# R122X.net
KiCad netlist of a schematic drawn in EAGLE
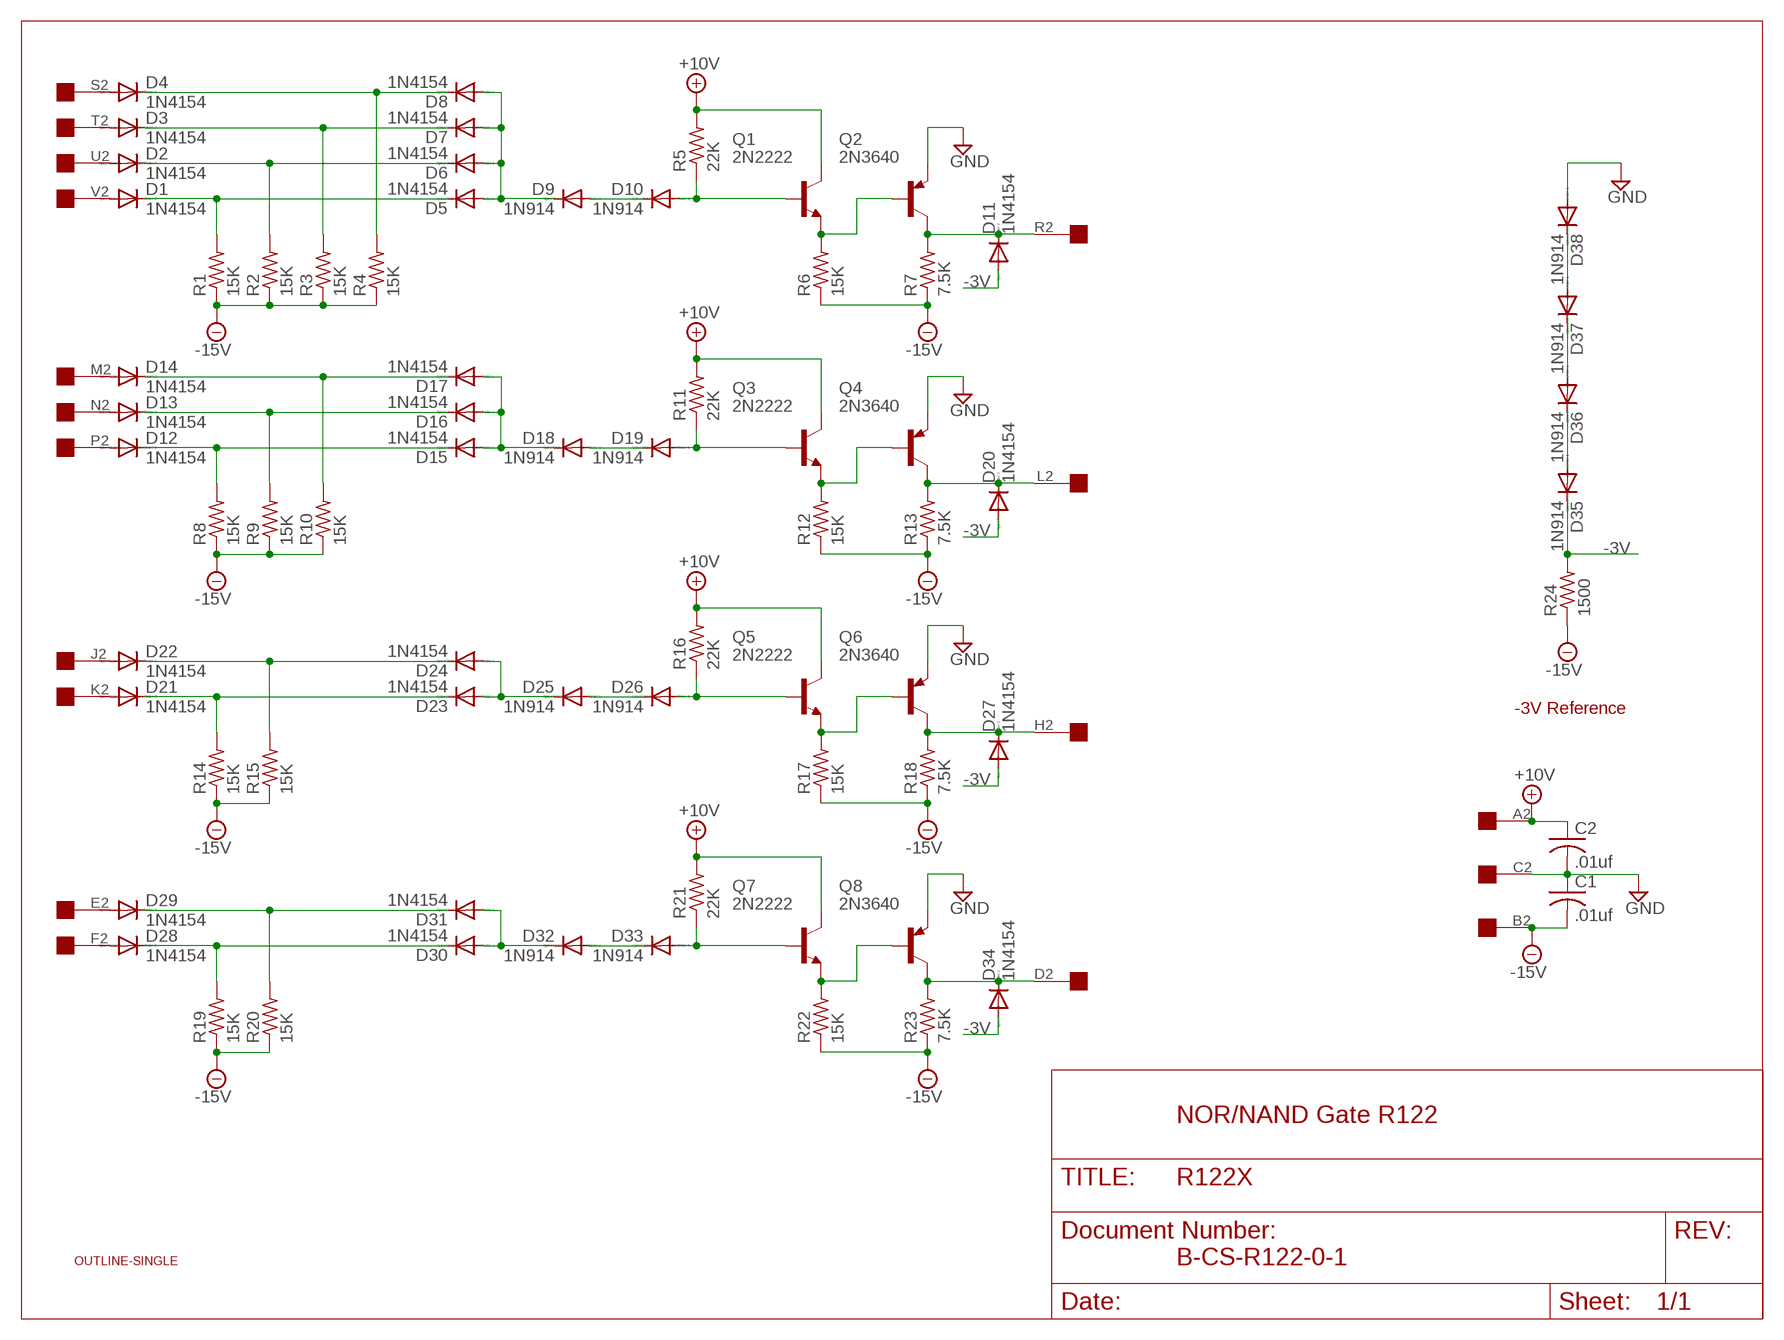
[diagram p0: schematic, sheet 1]

(export (version "E")
  (design (tool "Eeschema 10.0.6"))
  (components
    (comp (ref "C1")
      (value ".01uf")
      (footprint "eagle-import:C050-025X075")
      (libsource (lib "eagle-import") (part "C-US050-025X075"))
    )
    (comp (ref "C2")
      (value ".01uf")
      (footprint "eagle-import:C050-025X075")
      (libsource (lib "eagle-import") (part "C-US050-025X075"))
    )
    (comp (ref "D1")
      (value "1N4154")
      (footprint "eagle-import:DO35-10")
      (libsource (lib "eagle-import") (part "1N4148DO35-10"))
    )
    (comp (ref "D2")
      (value "1N4154")
      (footprint "eagle-import:DO35-10")
      (libsource (lib "eagle-import") (part "1N4148DO35-10"))
    )
    (comp (ref "D3")
      (value "1N4154")
      (footprint "eagle-import:DO35-10")
      (libsource (lib "eagle-import") (part "1N4148DO35-10"))
    )
    (comp (ref "D4")
      (value "1N4154")
      (footprint "eagle-import:DO35-10")
      (libsource (lib "eagle-import") (part "1N4148DO35-10"))
    )
    (comp (ref "D5")
      (value "1N4154")
      (footprint "eagle-import:DO35-10")
      (libsource (lib "eagle-import") (part "1N4148DO35-10"))
    )
    (comp (ref "D6")
      (value "1N4154")
      (footprint "eagle-import:DO35-10")
      (libsource (lib "eagle-import") (part "1N4148DO35-10"))
    )
    (comp (ref "D7")
      (value "1N4154")
      (footprint "eagle-import:DO35-10")
      (libsource (lib "eagle-import") (part "1N4148DO35-10"))
    )
    (comp (ref "D8")
      (value "1N4154")
      (footprint "eagle-import:DO35-10")
      (libsource (lib "eagle-import") (part "1N4148DO35-10"))
    )
    (comp (ref "D9")
      (value "1N914")
      (footprint "eagle-import:DO35-10")
      (libsource (lib "eagle-import") (part "1N4148DO35-10"))
    )
    (comp (ref "D10")
      (value "1N914")
      (footprint "eagle-import:DO35-10")
      (libsource (lib "eagle-import") (part "1N4148DO35-10"))
    )
    (comp (ref "D11")
      (value "1N4154")
      (footprint "eagle-import:DO35-10")
      (libsource (lib "eagle-import") (part "1N4148DO35-10"))
    )
    (comp (ref "D12")
      (value "1N4154")
      (footprint "eagle-import:DO35-10")
      (libsource (lib "eagle-import") (part "1N4148DO35-10"))
    )
    (comp (ref "D13")
      (value "1N4154")
      (footprint "eagle-import:DO35-10")
      (libsource (lib "eagle-import") (part "1N4148DO35-10"))
    )
    (comp (ref "D14")
      (value "1N4154")
      (footprint "eagle-import:DO35-10")
      (libsource (lib "eagle-import") (part "1N4148DO35-10"))
    )
    (comp (ref "D15")
      (value "1N4154")
      (footprint "eagle-import:DO35-10")
      (libsource (lib "eagle-import") (part "1N4148DO35-10"))
    )
    (comp (ref "D16")
      (value "1N4154")
      (footprint "eagle-import:DO35-10")
      (libsource (lib "eagle-import") (part "1N4148DO35-10"))
    )
    (comp (ref "D17")
      (value "1N4154")
      (footprint "eagle-import:DO35-10")
      (libsource (lib "eagle-import") (part "1N4148DO35-10"))
    )
    (comp (ref "D18")
      (value "1N914")
      (footprint "eagle-import:DO35-10")
      (libsource (lib "eagle-import") (part "1N4148DO35-10"))
    )
    (comp (ref "D19")
      (value "1N914")
      (footprint "eagle-import:DO35-10")
      (libsource (lib "eagle-import") (part "1N4148DO35-10"))
    )
    (comp (ref "D20")
      (value "1N4154")
      (footprint "eagle-import:DO35-10")
      (libsource (lib "eagle-import") (part "1N4148DO35-10"))
    )
    (comp (ref "D21")
      (value "1N4154")
      (footprint "eagle-import:DO35-10")
      (libsource (lib "eagle-import") (part "1N4148DO35-10"))
    )
    (comp (ref "D22")
      (value "1N4154")
      (footprint "eagle-import:DO35-10")
      (libsource (lib "eagle-import") (part "1N4148DO35-10"))
    )
    (comp (ref "D23")
      (value "1N4154")
      (footprint "eagle-import:DO35-10")
      (libsource (lib "eagle-import") (part "1N4148DO35-10"))
    )
    (comp (ref "D24")
      (value "1N4154")
      (footprint "eagle-import:DO35-10")
      (libsource (lib "eagle-import") (part "1N4148DO35-10"))
    )
    (comp (ref "D25")
      (value "1N914")
      (footprint "eagle-import:DO35-10")
      (libsource (lib "eagle-import") (part "1N4148DO35-10"))
    )
    (comp (ref "D26")
      (value "1N914")
      (footprint "eagle-import:DO35-10")
      (libsource (lib "eagle-import") (part "1N4148DO35-10"))
    )
    (comp (ref "D27")
      (value "1N4154")
      (footprint "eagle-import:DO35-10")
      (libsource (lib "eagle-import") (part "1N4148DO35-10"))
    )
    (comp (ref "D28")
      (value "1N4154")
      (footprint "eagle-import:DO35-10")
      (libsource (lib "eagle-import") (part "1N4148DO35-10"))
    )
    (comp (ref "D29")
      (value "1N4154")
      (footprint "eagle-import:DO35-10")
      (libsource (lib "eagle-import") (part "1N4148DO35-10"))
    )
    (comp (ref "D30")
      (value "1N4154")
      (footprint "eagle-import:DO35-10")
      (libsource (lib "eagle-import") (part "1N4148DO35-10"))
    )
    (comp (ref "D31")
      (value "1N4154")
      (footprint "eagle-import:DO35-10")
      (libsource (lib "eagle-import") (part "1N4148DO35-10"))
    )
    (comp (ref "D32")
      (value "1N914")
      (footprint "eagle-import:DO35-10")
      (libsource (lib "eagle-import") (part "1N4148DO35-10"))
    )
    (comp (ref "D33")
      (value "1N914")
      (footprint "eagle-import:DO35-10")
      (libsource (lib "eagle-import") (part "1N4148DO35-10"))
    )
    (comp (ref "D34")
      (value "1N4154")
      (footprint "eagle-import:DO35-10")
      (libsource (lib "eagle-import") (part "1N4148DO35-10"))
    )
    (comp (ref "D35")
      (value "1N914")
      (footprint "eagle-import:DO35-10")
      (libsource (lib "eagle-import") (part "1N4148DO35-10"))
    )
    (comp (ref "D36")
      (value "1N914")
      (footprint "eagle-import:DO35-10")
      (libsource (lib "eagle-import") (part "1N4148DO35-10"))
    )
    (comp (ref "D37")
      (value "1N914")
      (footprint "eagle-import:DO35-10")
      (libsource (lib "eagle-import") (part "1N4148DO35-10"))
    )
    (comp (ref "D38")
      (value "1N914")
      (footprint "eagle-import:DO35-10")
      (libsource (lib "eagle-import") (part "1N4148DO35-10"))
    )
    (comp (ref "Q1")
      (value "2N2222")
      (footprint "eagle-import:TO39")
      (libsource (lib "eagle-import") (part "-NPN-TO39-EBC2N1711"))
    )
    (comp (ref "Q2")
      (value "2N3640")
      (footprint "eagle-import:TO39")
      (libsource (lib "eagle-import") (part "2N3637"))
    )
    (comp (ref "Q3")
      (value "2N2222")
      (footprint "eagle-import:TO39")
      (libsource (lib "eagle-import") (part "-NPN-TO39-EBC2N1711"))
    )
    (comp (ref "Q4")
      (value "2N3640")
      (footprint "eagle-import:TO39")
      (libsource (lib "eagle-import") (part "2N3637"))
    )
    (comp (ref "Q5")
      (value "2N2222")
      (footprint "eagle-import:TO39")
      (libsource (lib "eagle-import") (part "-NPN-TO39-EBC2N1711"))
    )
    (comp (ref "Q6")
      (value "2N3640")
      (footprint "eagle-import:TO39")
      (libsource (lib "eagle-import") (part "2N3637"))
    )
    (comp (ref "Q7")
      (value "2N2222")
      (footprint "eagle-import:TO39")
      (libsource (lib "eagle-import") (part "-NPN-TO39-EBC2N1711"))
    )
    (comp (ref "Q8")
      (value "2N3640")
      (footprint "eagle-import:TO39")
      (libsource (lib "eagle-import") (part "2N3637"))
    )
    (comp (ref "R1")
      (value "15K")
      (footprint "eagle-import:0207_10")
      (libsource (lib "eagle-import") (part "R-US_0207/10"))
    )
    (comp (ref "R2")
      (value "15K")
      (footprint "eagle-import:0207_10")
      (libsource (lib "eagle-import") (part "R-US_0207/10"))
    )
    (comp (ref "R3")
      (value "15K")
      (footprint "eagle-import:0207_10")
      (libsource (lib "eagle-import") (part "R-US_0207/10"))
    )
    (comp (ref "R4")
      (value "15K")
      (footprint "eagle-import:0207_10")
      (libsource (lib "eagle-import") (part "R-US_0207/10"))
    )
    (comp (ref "R5")
      (value "22K")
      (footprint "eagle-import:0207_10")
      (libsource (lib "eagle-import") (part "R-US_0207/10"))
    )
    (comp (ref "R6")
      (value "15K")
      (footprint "eagle-import:0207_10")
      (libsource (lib "eagle-import") (part "R-US_0207/10"))
    )
    (comp (ref "R7")
      (value "7.5K")
      (footprint "eagle-import:0207_10")
      (libsource (lib "eagle-import") (part "R-US_0207/10"))
    )
    (comp (ref "R8")
      (value "15K")
      (footprint "eagle-import:0207_10")
      (libsource (lib "eagle-import") (part "R-US_0207/10"))
    )
    (comp (ref "R9")
      (value "15K")
      (footprint "eagle-import:0207_10")
      (libsource (lib "eagle-import") (part "R-US_0207/10"))
    )
    (comp (ref "R10")
      (value "15K")
      (footprint "eagle-import:0207_10")
      (libsource (lib "eagle-import") (part "R-US_0207/10"))
    )
    (comp (ref "R11")
      (value "22K")
      (footprint "eagle-import:0207_10")
      (libsource (lib "eagle-import") (part "R-US_0207/10"))
    )
    (comp (ref "R12")
      (value "15K")
      (footprint "eagle-import:0207_10")
      (libsource (lib "eagle-import") (part "R-US_0207/10"))
    )
    (comp (ref "R13")
      (value "7.5K")
      (footprint "eagle-import:0207_10")
      (libsource (lib "eagle-import") (part "R-US_0207/10"))
    )
    (comp (ref "R14")
      (value "15K")
      (footprint "eagle-import:0207_10")
      (libsource (lib "eagle-import") (part "R-US_0207/10"))
    )
    (comp (ref "R15")
      (value "15K")
      (footprint "eagle-import:0207_10")
      (libsource (lib "eagle-import") (part "R-US_0207/10"))
    )
    (comp (ref "R16")
      (value "22K")
      (footprint "eagle-import:0207_10")
      (libsource (lib "eagle-import") (part "R-US_0207/10"))
    )
    (comp (ref "R17")
      (value "15K")
      (footprint "eagle-import:0207_10")
      (libsource (lib "eagle-import") (part "R-US_0207/10"))
    )
    (comp (ref "R18")
      (value "7.5K")
      (footprint "eagle-import:0207_10")
      (libsource (lib "eagle-import") (part "R-US_0207/10"))
    )
    (comp (ref "R19")
      (value "15K")
      (footprint "eagle-import:0207_10")
      (libsource (lib "eagle-import") (part "R-US_0207/10"))
    )
    (comp (ref "R20")
      (value "15K")
      (footprint "eagle-import:0207_10")
      (libsource (lib "eagle-import") (part "R-US_0207/10"))
    )
    (comp (ref "R21")
      (value "22K")
      (footprint "eagle-import:0207_10")
      (libsource (lib "eagle-import") (part "R-US_0207/10"))
    )
    (comp (ref "R22")
      (value "15K")
      (footprint "eagle-import:0207_10")
      (libsource (lib "eagle-import") (part "R-US_0207/10"))
    )
    (comp (ref "R23")
      (value "7.5K")
      (footprint "eagle-import:0207_10")
      (libsource (lib "eagle-import") (part "R-US_0207/10"))
    )
    (comp (ref "R24")
      (value "1500")
      (footprint "eagle-import:0207_10")
      (libsource (lib "eagle-import") (part "R-US_0207/10"))
    )
    (comp (ref "U$1")
      (value "OUTLINE-SINGLE")
      (footprint "eagle-import:SINGLE")
      (libsource (lib "eagle-import") (part "OUTLINE-SINGLE"))
    )
    (comp (ref "U$2")
      (value "EDGE-1")
      (footprint "eagle-import:EDGE-CON1")
      (libsource (lib "eagle-import") (part "EDGE-1"))
    )
  )
  (nets
    (net (code "1") (name "+10V") (class "Default")
      (node (ref "C2") (pin "1") (pinfunction "1_1") (pintype "passive"))
      (node (ref "Q1") (pin "3") (pinfunction "C_3") (pintype "passive"))
      (node (ref "Q3") (pin "3") (pinfunction "C_3") (pintype "passive"))
      (node (ref "Q5") (pin "3") (pinfunction "C_3") (pintype "passive"))
      (node (ref "Q7") (pin "3") (pinfunction "C_3") (pintype "passive"))
      (node (ref "R11") (pin "2") (pinfunction "2_2") (pintype "passive"))
      (node (ref "R16") (pin "2") (pinfunction "2_2") (pintype "passive"))
      (node (ref "R21") (pin "2") (pinfunction "2_2") (pintype "passive"))
      (node (ref "R5") (pin "2") (pinfunction "2_2") (pintype "passive"))
      (node (ref "U$2") (pin "A2") (pinfunction "1_A2") (pintype "bidirectional"))
    )
    (net (code "2") (name "-15V") (class "Default")
      (node (ref "C1") (pin "2") (pinfunction "2_2") (pintype "passive"))
      (node (ref "R1") (pin "1") (pinfunction "1_1") (pintype "passive"))
      (node (ref "R10") (pin "1") (pinfunction "1_1") (pintype "passive"))
      (node (ref "R12") (pin "1") (pinfunction "1_1") (pintype "passive"))
      (node (ref "R13") (pin "1") (pinfunction "1_1") (pintype "passive"))
      (node (ref "R14") (pin "1") (pinfunction "1_1") (pintype "passive"))
      (node (ref "R15") (pin "1") (pinfunction "1_1") (pintype "passive"))
      (node (ref "R17") (pin "1") (pinfunction "1_1") (pintype "passive"))
      (node (ref "R18") (pin "1") (pinfunction "1_1") (pintype "passive"))
      (node (ref "R19") (pin "1") (pinfunction "1_1") (pintype "passive"))
      (node (ref "R2") (pin "1") (pinfunction "1_1") (pintype "passive"))
      (node (ref "R20") (pin "1") (pinfunction "1_1") (pintype "passive"))
      (node (ref "R22") (pin "1") (pinfunction "1_1") (pintype "passive"))
      (node (ref "R23") (pin "1") (pinfunction "1_1") (pintype "passive"))
      (node (ref "R24") (pin "1") (pinfunction "1_1") (pintype "passive"))
      (node (ref "R3") (pin "1") (pinfunction "1_1") (pintype "passive"))
      (node (ref "R4") (pin "1") (pinfunction "1_1") (pintype "passive"))
      (node (ref "R6") (pin "1") (pinfunction "1_1") (pintype "passive"))
      (node (ref "R7") (pin "1") (pinfunction "1_1") (pintype "passive"))
      (node (ref "R8") (pin "1") (pinfunction "1_1") (pintype "passive"))
      (node (ref "R9") (pin "1") (pinfunction "1_1") (pintype "passive"))
      (node (ref "U$2") (pin "B2") (pinfunction "1_B2") (pintype "bidirectional"))
    )
    (net (code "3") (name "/-3V") (class "Default")
      (node (ref "D11") (pin "A") (pinfunction "A_A") (pintype "passive"))
      (node (ref "D20") (pin "A") (pinfunction "A_A") (pintype "passive"))
      (node (ref "D27") (pin "A") (pinfunction "A_A") (pintype "passive"))
      (node (ref "D34") (pin "A") (pinfunction "A_A") (pintype "passive"))
      (node (ref "D35") (pin "C") (pinfunction "C_C") (pintype "passive"))
      (node (ref "R24") (pin "2") (pinfunction "2_2") (pintype "passive"))
    )
    (net (code "4") (name "GND") (class "Default")
      (node (ref "C1") (pin "1") (pinfunction "1_1") (pintype "passive"))
      (node (ref "C2") (pin "2") (pinfunction "2_2") (pintype "passive"))
      (node (ref "D38") (pin "A") (pinfunction "A_A") (pintype "passive"))
      (node (ref "Q2") (pin "1") (pinfunction "E_1") (pintype "passive"))
      (node (ref "Q4") (pin "1") (pinfunction "E_1") (pintype "passive"))
      (node (ref "Q6") (pin "1") (pinfunction "E_1") (pintype "passive"))
      (node (ref "Q8") (pin "1") (pinfunction "E_1") (pintype "passive"))
      (node (ref "U$2") (pin "C2") (pinfunction "1_C2") (pintype "bidirectional"))
    )
    (net (code "5") (name "Net-(D1-PadC)") (class "Default")
      (node (ref "D1") (pin "C") (pinfunction "C_C") (pintype "passive"))
      (node (ref "D5") (pin "C") (pinfunction "C_C") (pintype "passive"))
      (node (ref "R1") (pin "2") (pinfunction "2_2") (pintype "passive"))
    )
    (net (code "6") (name "Net-(D2-PadC)") (class "Default")
      (node (ref "D2") (pin "C") (pinfunction "C_C") (pintype "passive"))
      (node (ref "D6") (pin "C") (pinfunction "C_C") (pintype "passive"))
      (node (ref "R2") (pin "2") (pinfunction "2_2") (pintype "passive"))
    )
    (net (code "7") (name "Net-(D3-PadC)") (class "Default")
      (node (ref "D3") (pin "C") (pinfunction "C_C") (pintype "passive"))
      (node (ref "D7") (pin "C") (pinfunction "C_C") (pintype "passive"))
      (node (ref "R3") (pin "2") (pinfunction "2_2") (pintype "passive"))
    )
    (net (code "8") (name "Net-(D4-PadC)") (class "Default")
      (node (ref "D4") (pin "C") (pinfunction "C_C") (pintype "passive"))
      (node (ref "D8") (pin "C") (pinfunction "C_C") (pintype "passive"))
      (node (ref "R4") (pin "2") (pinfunction "2_2") (pintype "passive"))
    )
    (net (code "9") (name "Net-(D5-PadA)") (class "Default")
      (node (ref "D5") (pin "A") (pinfunction "A_A") (pintype "passive"))
      (node (ref "D6") (pin "A") (pinfunction "A_A") (pintype "passive"))
      (node (ref "D7") (pin "A") (pinfunction "A_A") (pintype "passive"))
      (node (ref "D8") (pin "A") (pinfunction "A_A") (pintype "passive"))
      (node (ref "D9") (pin "C") (pinfunction "C_C") (pintype "passive"))
    )
    (net (code "10") (name "Net-(D10-PadC)") (class "Default")
      (node (ref "D10") (pin "C") (pinfunction "C_C") (pintype "passive"))
      (node (ref "D9") (pin "A") (pinfunction "A_A") (pintype "passive"))
    )
    (net (code "11") (name "Net-(D12-PadC)") (class "Default")
      (node (ref "D12") (pin "C") (pinfunction "C_C") (pintype "passive"))
      (node (ref "D15") (pin "C") (pinfunction "C_C") (pintype "passive"))
      (node (ref "R8") (pin "2") (pinfunction "2_2") (pintype "passive"))
    )
    (net (code "12") (name "Net-(D13-PadC)") (class "Default")
      (node (ref "D13") (pin "C") (pinfunction "C_C") (pintype "passive"))
      (node (ref "D16") (pin "C") (pinfunction "C_C") (pintype "passive"))
      (node (ref "R9") (pin "2") (pinfunction "2_2") (pintype "passive"))
    )
    (net (code "13") (name "Net-(D14-PadC)") (class "Default")
      (node (ref "D14") (pin "C") (pinfunction "C_C") (pintype "passive"))
      (node (ref "D17") (pin "C") (pinfunction "C_C") (pintype "passive"))
      (node (ref "R10") (pin "2") (pinfunction "2_2") (pintype "passive"))
    )
    (net (code "14") (name "Net-(D15-PadA)") (class "Default")
      (node (ref "D15") (pin "A") (pinfunction "A_A") (pintype "passive"))
      (node (ref "D16") (pin "A") (pinfunction "A_A") (pintype "passive"))
      (node (ref "D17") (pin "A") (pinfunction "A_A") (pintype "passive"))
      (node (ref "D18") (pin "C") (pinfunction "C_C") (pintype "passive"))
    )
    (net (code "15") (name "Net-(D18-PadA)") (class "Default")
      (node (ref "D18") (pin "A") (pinfunction "A_A") (pintype "passive"))
      (node (ref "D19") (pin "C") (pinfunction "C_C") (pintype "passive"))
    )
    (net (code "16") (name "Net-(D21-PadC)") (class "Default")
      (node (ref "D21") (pin "C") (pinfunction "C_C") (pintype "passive"))
      (node (ref "D23") (pin "C") (pinfunction "C_C") (pintype "passive"))
      (node (ref "R14") (pin "2") (pinfunction "2_2") (pintype "passive"))
    )
    (net (code "17") (name "Net-(D22-PadC)") (class "Default")
      (node (ref "D22") (pin "C") (pinfunction "C_C") (pintype "passive"))
      (node (ref "D24") (pin "C") (pinfunction "C_C") (pintype "passive"))
      (node (ref "R15") (pin "2") (pinfunction "2_2") (pintype "passive"))
    )
    (net (code "18") (name "Net-(D23-PadA)") (class "Default")
      (node (ref "D23") (pin "A") (pinfunction "A_A") (pintype "passive"))
      (node (ref "D24") (pin "A") (pinfunction "A_A") (pintype "passive"))
      (node (ref "D25") (pin "C") (pinfunction "C_C") (pintype "passive"))
    )
    (net (code "19") (name "Net-(D25-PadA)") (class "Default")
      (node (ref "D25") (pin "A") (pinfunction "A_A") (pintype "passive"))
      (node (ref "D26") (pin "C") (pinfunction "C_C") (pintype "passive"))
    )
    (net (code "20") (name "Net-(D28-PadC)") (class "Default")
      (node (ref "D28") (pin "C") (pinfunction "C_C") (pintype "passive"))
      (node (ref "D30") (pin "C") (pinfunction "C_C") (pintype "passive"))
      (node (ref "R19") (pin "2") (pinfunction "2_2") (pintype "passive"))
    )
    (net (code "21") (name "Net-(D29-PadC)") (class "Default")
      (node (ref "D29") (pin "C") (pinfunction "C_C") (pintype "passive"))
      (node (ref "D31") (pin "C") (pinfunction "C_C") (pintype "passive"))
      (node (ref "R20") (pin "2") (pinfunction "2_2") (pintype "passive"))
    )
    (net (code "22") (name "Net-(D30-PadA)") (class "Default")
      (node (ref "D30") (pin "A") (pinfunction "A_A") (pintype "passive"))
      (node (ref "D31") (pin "A") (pinfunction "A_A") (pintype "passive"))
      (node (ref "D32") (pin "C") (pinfunction "C_C") (pintype "passive"))
    )
    (net (code "23") (name "Net-(D32-PadA)") (class "Default")
      (node (ref "D32") (pin "A") (pinfunction "A_A") (pintype "passive"))
      (node (ref "D33") (pin "C") (pinfunction "C_C") (pintype "passive"))
    )
    (net (code "24") (name "Net-(D35-PadA)") (class "Default")
      (node (ref "D35") (pin "A") (pinfunction "A_A") (pintype "passive"))
      (node (ref "D36") (pin "C") (pinfunction "C_C") (pintype "passive"))
    )
    (net (code "25") (name "Net-(D36-PadA)") (class "Default")
      (node (ref "D36") (pin "A") (pinfunction "A_A") (pintype "passive"))
      (node (ref "D37") (pin "C") (pinfunction "C_C") (pintype "passive"))
    )
    (net (code "26") (name "Net-(D37-PadA)") (class "Default")
      (node (ref "D37") (pin "A") (pinfunction "A_A") (pintype "passive"))
      (node (ref "D38") (pin "C") (pinfunction "C_C") (pintype "passive"))
    )
    (net (code "27") (name "Net-(Q1-B)") (class "Default")
      (node (ref "D10") (pin "A") (pinfunction "A_A") (pintype "passive"))
      (node (ref "Q1") (pin "2") (pinfunction "B_2") (pintype "passive"))
      (node (ref "R5") (pin "1") (pinfunction "1_1") (pintype "passive"))
    )
    (net (code "28") (name "Net-(Q1-E)") (class "Default")
      (node (ref "Q1") (pin "1") (pinfunction "E_1") (pintype "passive"))
      (node (ref "Q2") (pin "2") (pinfunction "B_2") (pintype "passive"))
      (node (ref "R6") (pin "2") (pinfunction "2_2") (pintype "passive"))
    )
    (net (code "29") (name "Net-(Q2-C)") (class "Default")
      (node (ref "D11") (pin "C") (pinfunction "C_C") (pintype "passive"))
      (node (ref "Q2") (pin "3") (pinfunction "C_3") (pintype "passive"))
      (node (ref "R7") (pin "2") (pinfunction "2_2") (pintype "passive"))
      (node (ref "U$2") (pin "R2") (pinfunction "1_R2") (pintype "bidirectional"))
    )
    (net (code "30") (name "Net-(Q3-B)") (class "Default")
      (node (ref "D19") (pin "A") (pinfunction "A_A") (pintype "passive"))
      (node (ref "Q3") (pin "2") (pinfunction "B_2") (pintype "passive"))
      (node (ref "R11") (pin "1") (pinfunction "1_1") (pintype "passive"))
    )
    (net (code "31") (name "Net-(Q3-E)") (class "Default")
      (node (ref "Q3") (pin "1") (pinfunction "E_1") (pintype "passive"))
      (node (ref "Q4") (pin "2") (pinfunction "B_2") (pintype "passive"))
      (node (ref "R12") (pin "2") (pinfunction "2_2") (pintype "passive"))
    )
    (net (code "32") (name "Net-(Q4-C)") (class "Default")
      (node (ref "D20") (pin "C") (pinfunction "C_C") (pintype "passive"))
      (node (ref "Q4") (pin "3") (pinfunction "C_3") (pintype "passive"))
      (node (ref "R13") (pin "2") (pinfunction "2_2") (pintype "passive"))
      (node (ref "U$2") (pin "L2") (pinfunction "1_L2") (pintype "bidirectional"))
    )
    (net (code "33") (name "Net-(Q5-B)") (class "Default")
      (node (ref "D26") (pin "A") (pinfunction "A_A") (pintype "passive"))
      (node (ref "Q5") (pin "2") (pinfunction "B_2") (pintype "passive"))
      (node (ref "R16") (pin "1") (pinfunction "1_1") (pintype "passive"))
    )
    (net (code "34") (name "Net-(Q5-E)") (class "Default")
      (node (ref "Q5") (pin "1") (pinfunction "E_1") (pintype "passive"))
      (node (ref "Q6") (pin "2") (pinfunction "B_2") (pintype "passive"))
      (node (ref "R17") (pin "2") (pinfunction "2_2") (pintype "passive"))
    )
    (net (code "35") (name "Net-(Q6-C)") (class "Default")
      (node (ref "D27") (pin "C") (pinfunction "C_C") (pintype "passive"))
      (node (ref "Q6") (pin "3") (pinfunction "C_3") (pintype "passive"))
      (node (ref "R18") (pin "2") (pinfunction "2_2") (pintype "passive"))
      (node (ref "U$2") (pin "H2") (pinfunction "1_H2") (pintype "bidirectional"))
    )
    (net (code "36") (name "Net-(Q7-B)") (class "Default")
      (node (ref "D33") (pin "A") (pinfunction "A_A") (pintype "passive"))
      (node (ref "Q7") (pin "2") (pinfunction "B_2") (pintype "passive"))
      (node (ref "R21") (pin "1") (pinfunction "1_1") (pintype "passive"))
    )
    (net (code "37") (name "Net-(Q7-E)") (class "Default")
      (node (ref "Q7") (pin "1") (pinfunction "E_1") (pintype "passive"))
      (node (ref "Q8") (pin "2") (pinfunction "B_2") (pintype "passive"))
      (node (ref "R22") (pin "2") (pinfunction "2_2") (pintype "passive"))
    )
    (net (code "38") (name "Net-(Q8-C)") (class "Default")
      (node (ref "D34") (pin "C") (pinfunction "C_C") (pintype "passive"))
      (node (ref "Q8") (pin "3") (pinfunction "C_3") (pintype "passive"))
      (node (ref "R23") (pin "2") (pinfunction "2_2") (pintype "passive"))
      (node (ref "U$2") (pin "D2") (pinfunction "1_D2") (pintype "bidirectional"))
    )
    (net (code "39") (name "Net-(U$2E-1)") (class "Default")
      (node (ref "D29") (pin "A") (pinfunction "A_A") (pintype "passive"))
      (node (ref "U$2") (pin "E2") (pinfunction "1_E2") (pintype "bidirectional"))
    )
    (net (code "40") (name "Net-(U$2F-1)") (class "Default")
      (node (ref "D28") (pin "A") (pinfunction "A_A") (pintype "passive"))
      (node (ref "U$2") (pin "F2") (pinfunction "1_F2") (pintype "bidirectional"))
    )
    (net (code "41") (name "Net-(U$2H-1)") (class "Default")
      (node (ref "D22") (pin "A") (pinfunction "A_A") (pintype "passive"))
      (node (ref "U$2") (pin "J2") (pinfunction "1_J2") (pintype "bidirectional"))
    )
    (net (code "42") (name "Net-(U$2I-1)") (class "Default")
      (node (ref "D21") (pin "A") (pinfunction "A_A") (pintype "passive"))
      (node (ref "U$2") (pin "K2") (pinfunction "1_K2") (pintype "bidirectional"))
    )
    (net (code "43") (name "Net-(U$2K-1)") (class "Default")
      (node (ref "D14") (pin "A") (pinfunction "A_A") (pintype "passive"))
      (node (ref "U$2") (pin "M2") (pinfunction "1_M2") (pintype "bidirectional"))
    )
    (net (code "44") (name "Net-(U$2L-1)") (class "Default")
      (node (ref "D13") (pin "A") (pinfunction "A_A") (pintype "passive"))
      (node (ref "U$2") (pin "N2") (pinfunction "1_N2") (pintype "bidirectional"))
    )
    (net (code "45") (name "Net-(U$2M-1)") (class "Default")
      (node (ref "D12") (pin "A") (pinfunction "A_A") (pintype "passive"))
      (node (ref "U$2") (pin "P2") (pinfunction "1_P2") (pintype "bidirectional"))
    )
    (net (code "46") (name "Net-(U$2O-1)") (class "Default")
      (node (ref "D4") (pin "A") (pinfunction "A_A") (pintype "passive"))
      (node (ref "U$2") (pin "S2") (pinfunction "1_S2") (pintype "bidirectional"))
    )
    (net (code "47") (name "Net-(U$2P-1)") (class "Default")
      (node (ref "D3") (pin "A") (pinfunction "A_A") (pintype "passive"))
      (node (ref "U$2") (pin "T2") (pinfunction "1_T2") (pintype "bidirectional"))
    )
    (net (code "48") (name "Net-(U$2Q-1)") (class "Default")
      (node (ref "D2") (pin "A") (pinfunction "A_A") (pintype "passive"))
      (node (ref "U$2") (pin "U2") (pinfunction "1_U2") (pintype "bidirectional"))
    )
    (net (code "49") (name "Net-(U$2R-1)") (class "Default")
      (node (ref "D1") (pin "A") (pinfunction "A_A") (pintype "passive"))
      (node (ref "U$2") (pin "V2") (pinfunction "1_V2") (pintype "bidirectional"))
    )
  )
)
